# mach.net
KiCad netlist of a schematic drawn in Altium Designer
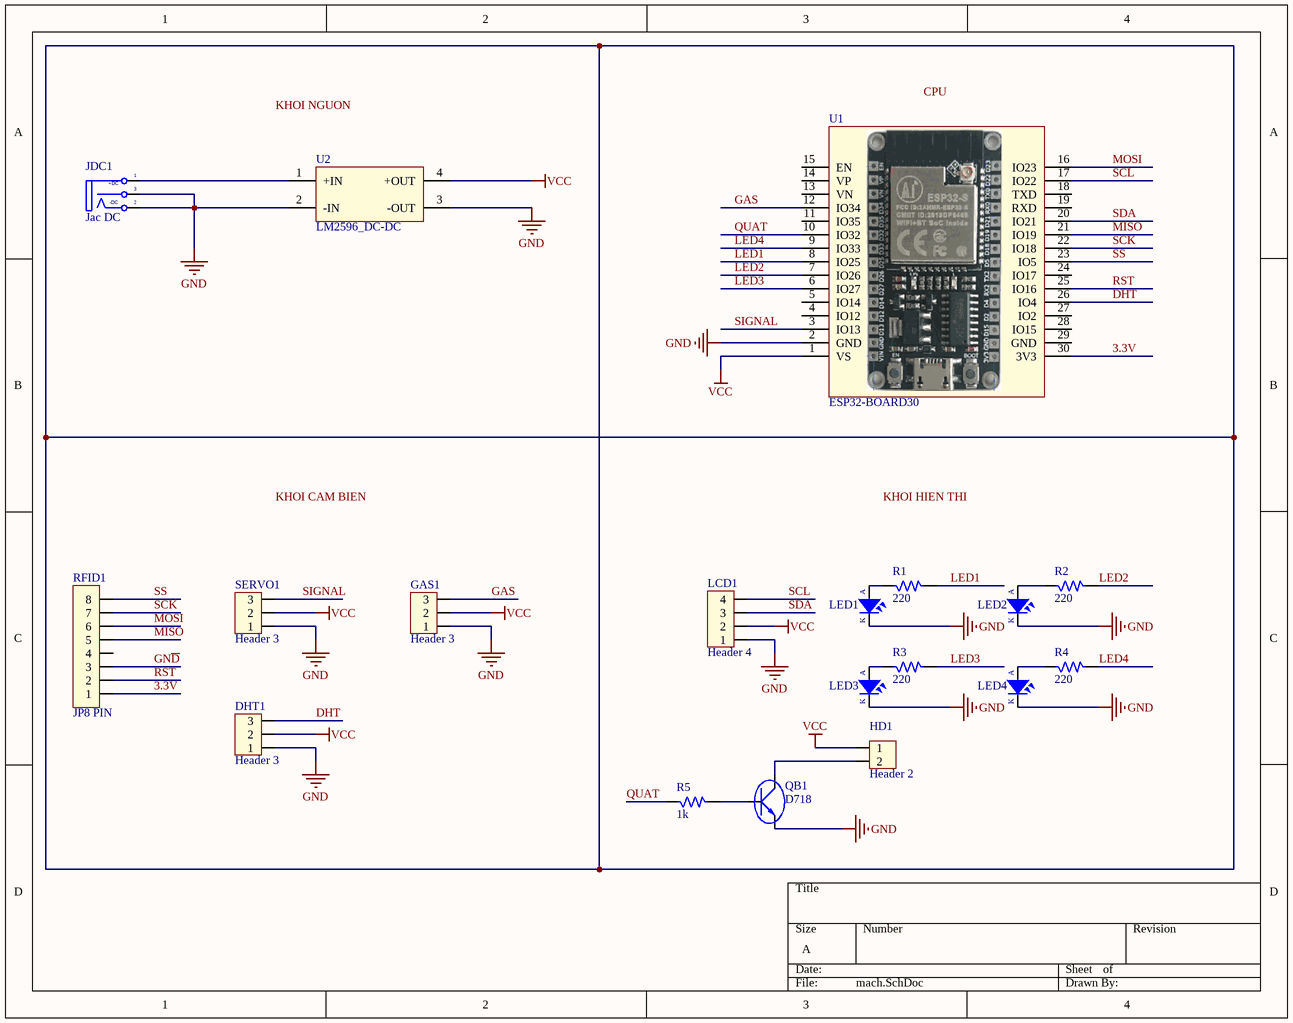
[diagram p0: mach.SchDoc]

(export (version "E")
  (design (tool "Eeschema 10.0.6"))
  (components
    (comp (ref "DHT1")
      (value "Header 3")
      (footprint "HED3")
      (description "Header 3 (Green)")
      (libsource (lib "PART_VDE") (part "Hed3"))
    )
    (comp (ref "GAS1")
      (value "Header 3")
      (footprint "HED3")
      (description "Header 3 (Green)")
      (libsource (lib "PART_VDE") (part "Hed3"))
    )
    (comp (ref "HD1")
      (value "Header 2")
      (footprint "HED2")
      (description "Header 2 (Green)")
      (libsource (lib "PART_VDE") (part "Hed2"))
    )
    (comp (ref "JDC1")
      (value "Jac DC")
      (footprint "DC-IN")
      (description "Jac DC input")
      (libsource (lib "PART_VDE") (part "DCIN"))
    )
    (comp (ref "LCD1")
      (value "Header 4")
      (footprint "KF8500-4P")
      (description "Header 4 (Green)")
      (libsource (lib "PART_VDE") (part "Hed4"))
    )
    (comp (ref "LED1")
      (value "~")
      (footprint "LED-5")
      (description "LED Single colour Green and Red")
      (libsource (lib "PART_VDE") (part "LED"))
    )
    (comp (ref "LED2")
      (value "~")
      (footprint "LED-5")
      (description "LED Single colour Green and Red")
      (libsource (lib "PART_VDE") (part "LED"))
    )
    (comp (ref "LED3")
      (value "~")
      (footprint "LED-5")
      (description "LED Single colour Green and Red")
      (libsource (lib "PART_VDE") (part "LED"))
    )
    (comp (ref "LED4")
      (value "~")
      (footprint "LED-5")
      (description "LED Single colour Green and Red")
      (libsource (lib "PART_VDE") (part "LED"))
    )
    (comp (ref "QB1")
      (value "D718")
      (footprint "QTO-247")
      (description "Transistor Power Supply")
      (libsource (lib "PART_VDE") (part "D718"))
    )
    (comp (ref "R1")
      (value "220")
      (footprint "RM-0805")
      (description "Resistor 1/4W")
      (libsource (lib "PART_VDE") (part "R"))
    )
    (comp (ref "R2")
      (value "220")
      (footprint "RM-0805")
      (description "Resistor 1/4W")
      (libsource (lib "PART_VDE") (part "R"))
    )
    (comp (ref "R3")
      (value "220")
      (footprint "RM-0805")
      (description "Resistor 1/4W")
      (libsource (lib "PART_VDE") (part "R"))
    )
    (comp (ref "R4")
      (value "220")
      (footprint "RM-0805")
      (description "Resistor 1/4W")
      (libsource (lib "PART_VDE") (part "R"))
    )
    (comp (ref "R5")
      (value "1k")
      (footprint "RM-0805")
      (description "Resistor 1/4W")
      (libsource (lib "PART_VDE") (part "R"))
    )
    (comp (ref "RFID1") (value "JP8 PIN") (footprint "JP8") (libsource (lib "PART_VDE") (part "JP8")))
    (comp (ref "SERVO1")
      (value "Header 3")
      (footprint "HED3")
      (description "Header 3 (Green)")
      (libsource (lib "PART_VDE") (part "Hed3"))
    )
    (comp (ref "U1")
      (value "ESP32-BOARD30")
      (footprint "ESP32-BOARD30-900")
      (libsource (lib "PART_VDE") (part "ESP32-BOARD30"))
    )
    (comp (ref "U2")
      (value "LM2596_DC-DC")
      (footprint "LM2596-DCDC")
      (description "Module LM2596_DC-DC")
      (libsource (lib "PART_VDE") (part "LM2596S DC-DC"))
    )
  )
  (nets
    (net (code "1") (name "/3.3V") (class "Default")
      (node (ref "RFID1") (pin "1") (pinfunction "1_1") (pintype "passive"))
      (node (ref "U1") (pin "30") (pinfunction "3V3_30") (pintype "passive"))
    )
    (net (code "4") (name "/DHT") (class "Default")
      (node (ref "DHT1") (pin "3") (pinfunction "3_3") (pintype "passive"))
      (node (ref "U1") (pin "26") (pinfunction "IO4_26") (pintype "passive"))
    )
    (net (code "5") (name "/GAS") (class "Default")
      (node (ref "GAS1") (pin "3") (pinfunction "3_3") (pintype "passive"))
      (node (ref "U1") (pin "12") (pinfunction "IO34_12") (pintype "passive"))
    )
    (net (code "6") (name "/GN~{D}") (class "Default")
      (node (ref "RFID1") (pin "3") (pinfunction "3_3") (pintype "passive"))
    )
    (net (code "10") (name "/LED1") (class "Default")
      (node (ref "R1") (pin "2") (pinfunction "2_2") (pintype "passive"))
      (node (ref "U1") (pin "8") (pinfunction "IO25_8") (pintype "passive"))
    )
    (net (code "11") (name "/LED2") (class "Default")
      (node (ref "R2") (pin "2") (pinfunction "2_2") (pintype "passive"))
      (node (ref "U1") (pin "7") (pinfunction "IO26_7") (pintype "passive"))
    )
    (net (code "12") (name "/LED3") (class "Default")
      (node (ref "R3") (pin "2") (pinfunction "2_2") (pintype "passive"))
      (node (ref "U1") (pin "6") (pinfunction "IO27_6") (pintype "passive"))
    )
    (net (code "13") (name "/LED4") (class "Default")
      (node (ref "R4") (pin "2") (pinfunction "2_2") (pintype "passive"))
      (node (ref "U1") (pin "9") (pinfunction "IO33_9") (pintype "passive"))
    )
    (net (code "14") (name "/MISO") (class "Default")
      (node (ref "RFID1") (pin "5") (pinfunction "5_5") (pintype "passive"))
      (node (ref "U1") (pin "21") (pinfunction "IO19_21") (pintype "passive"))
    )
    (net (code "15") (name "/MOSI") (class "Default")
      (node (ref "RFID1") (pin "6") (pinfunction "6_6") (pintype "passive"))
      (node (ref "U1") (pin "16") (pinfunction "IO23_16") (pintype "passive"))
    )
    (net (code "16") (name "/QUAT") (class "Default")
      (node (ref "R5") (pin "1") (pinfunction "1_1") (pintype "passive"))
      (node (ref "U1") (pin "10") (pinfunction "IO32_10") (pintype "passive"))
    )
    (net (code "17") (name "/RST") (class "Default")
      (node (ref "RFID1") (pin "2") (pinfunction "2_2") (pintype "passive"))
      (node (ref "U1") (pin "25") (pinfunction "IO16_25") (pintype "passive"))
    )
    (net (code "18") (name "/SCK") (class "Default")
      (node (ref "RFID1") (pin "7") (pinfunction "7_7") (pintype "passive"))
      (node (ref "U1") (pin "22") (pinfunction "IO18_22") (pintype "passive"))
    )
    (net (code "19") (name "/SCL") (class "Default")
      (node (ref "LCD1") (pin "4") (pinfunction "4_4") (pintype "passive"))
      (node (ref "U1") (pin "17") (pinfunction "IO22_17") (pintype "passive"))
    )
    (net (code "20") (name "/SDA") (class "Default")
      (node (ref "LCD1") (pin "3") (pinfunction "3_3") (pintype "passive"))
      (node (ref "U1") (pin "20") (pinfunction "IO21_20") (pintype "passive"))
    )
    (net (code "21") (name "/SIGNAL") (class "Default")
      (node (ref "SERVO1") (pin "3") (pinfunction "3_3") (pintype "passive"))
      (node (ref "U1") (pin "3") (pinfunction "IO13_3") (pintype "passive"))
    )
    (net (code "22") (name "/SS") (class "Default")
      (node (ref "RFID1") (pin "8") (pinfunction "8_8") (pintype "passive"))
      (node (ref "U1") (pin "23") (pinfunction "IO5_23") (pintype "passive"))
    )
    (net (code "23") (name "GND") (class "Default")
      (node (ref "DHT1") (pin "1") (pinfunction "1_1") (pintype "passive"))
      (node (ref "GAS1") (pin "1") (pinfunction "1_1") (pintype "passive"))
      (node (ref "JDC1") (pin "2") (pinfunction "TN_2") (pintype "passive"))
      (node (ref "JDC1") (pin "3") (pinfunction "S_3") (pintype "power_in"))
      (node (ref "LCD1") (pin "1") (pinfunction "1_1") (pintype "passive"))
      (node (ref "LED1") (pin "2") (pinfunction "K_2") (pintype "passive"))
      (node (ref "LED2") (pin "2") (pinfunction "K_2") (pintype "passive"))
      (node (ref "LED3") (pin "2") (pinfunction "K_2") (pintype "passive"))
      (node (ref "LED4") (pin "2") (pinfunction "K_2") (pintype "passive"))
      (node (ref "QB1") (pin "3") (pinfunction "E_3") (pintype "passive"))
      (node (ref "SERVO1") (pin "1") (pinfunction "1_1") (pintype "passive"))
      (node (ref "U1") (pin "2") (pinfunction "GND_2") (pintype "passive"))
      (node (ref "U2") (pin "2") (pinfunction "-IN_2") (pintype "passive"))
      (node (ref "U2") (pin "3") (pinfunction "-OUT_3") (pintype "passive"))
    )
    (net (code "24") (name "Net-(JDC1-+DC)") (class "Default")
      (node (ref "JDC1") (pin "1") (pinfunction "+DC_1") (pintype "passive"))
      (node (ref "U2") (pin "1") (pinfunction "+IN_1") (pintype "passive"))
    )
    (net (code "25") (name "Net-(LED1-A)") (class "Default")
      (node (ref "LED1") (pin "1") (pinfunction "A_1") (pintype "passive"))
      (node (ref "R1") (pin "1") (pinfunction "1_1") (pintype "passive"))
    )
    (net (code "26") (name "Net-(LED2-A)") (class "Default")
      (node (ref "LED2") (pin "1") (pinfunction "A_1") (pintype "passive"))
      (node (ref "R2") (pin "1") (pinfunction "1_1") (pintype "passive"))
    )
    (net (code "27") (name "Net-(LED3-A)") (class "Default")
      (node (ref "LED3") (pin "1") (pinfunction "A_1") (pintype "passive"))
      (node (ref "R3") (pin "1") (pinfunction "1_1") (pintype "passive"))
    )
    (net (code "28") (name "Net-(LED4-A)") (class "Default")
      (node (ref "LED4") (pin "1") (pinfunction "A_1") (pintype "passive"))
      (node (ref "R4") (pin "1") (pinfunction "1_1") (pintype "passive"))
    )
    (net (code "29") (name "Net-(QB1-B)") (class "Default")
      (node (ref "QB1") (pin "1") (pinfunction "B_1") (pintype "passive"))
      (node (ref "R5") (pin "2") (pinfunction "2_2") (pintype "passive"))
    )
    (net (code "30") (name "Net-(QB1-C)") (class "Default")
      (node (ref "HD1") (pin "2") (pinfunction "2_2") (pintype "passive"))
      (node (ref "QB1") (pin "2") (pinfunction "C_2") (pintype "passive"))
    )
    (net (code "31") (name "VCC") (class "Default")
      (node (ref "DHT1") (pin "2") (pinfunction "2_2") (pintype "passive"))
      (node (ref "GAS1") (pin "2") (pinfunction "2_2") (pintype "passive"))
      (node (ref "HD1") (pin "1") (pinfunction "1_1") (pintype "passive"))
      (node (ref "LCD1") (pin "2") (pinfunction "2_2") (pintype "passive"))
      (node (ref "SERVO1") (pin "2") (pinfunction "2_2") (pintype "passive"))
      (node (ref "U1") (pin "1") (pinfunction "VS_1") (pintype "passive"))
      (node (ref "U2") (pin "4") (pinfunction "+OUT_4") (pintype "passive"))
    )
    (net (code "32") (name "unconnected-(RFID1-Pad4)") (class "Default")
      (node (ref "RFID1") (pin "4") (pinfunction "4_4") (pintype "passive"))
    )
    (net (code "33") (name "unconnected-(U1-EN-Pad15)") (class "Default")
      (node (ref "U1") (pin "15") (pinfunction "EN_15") (pintype "passive"))
    )
    (net (code "34") (name "unconnected-(U1-GND-Pad29)") (class "Default")
      (node (ref "U1") (pin "29") (pinfunction "GND_29") (pintype "passive"))
    )
    (net (code "35") (name "unconnected-(U1-IO2-Pad27)") (class "Default")
      (node (ref "U1") (pin "27") (pinfunction "IO2_27") (pintype "passive"))
    )
    (net (code "36") (name "unconnected-(U1-IO12-Pad4)") (class "Default")
      (node (ref "U1") (pin "4") (pinfunction "IO12_4") (pintype "passive"))
    )
    (net (code "37") (name "unconnected-(U1-IO14-Pad5)") (class "Default")
      (node (ref "U1") (pin "5") (pinfunction "IO14_5") (pintype "passive"))
    )
    (net (code "38") (name "unconnected-(U1-IO15-Pad28)") (class "Default")
      (node (ref "U1") (pin "28") (pinfunction "IO15_28") (pintype "passive"))
    )
    (net (code "39") (name "unconnected-(U1-IO17-Pad24)") (class "Default")
      (node (ref "U1") (pin "24") (pinfunction "IO17_24") (pintype "passive"))
    )
    (net (code "40") (name "unconnected-(U1-IO35-Pad11)") (class "Default")
      (node (ref "U1") (pin "11") (pinfunction "IO35_11") (pintype "passive"))
    )
    (net (code "41") (name "unconnected-(U1-RXD-Pad19)") (class "Default")
      (node (ref "U1") (pin "19") (pinfunction "RXD_19") (pintype "passive"))
    )
    (net (code "42") (name "unconnected-(U1-TXD-Pad18)") (class "Default")
      (node (ref "U1") (pin "18") (pinfunction "TXD_18") (pintype "passive"))
    )
    (net (code "43") (name "unconnected-(U1-VN-Pad13)") (class "Default")
      (node (ref "U1") (pin "13") (pinfunction "VN_13") (pintype "passive"))
    )
    (net (code "44") (name "unconnected-(U1-VP-Pad14)") (class "Default")
      (node (ref "U1") (pin "14") (pinfunction "VP_14") (pintype "passive"))
    )
  )
)
